# GaugeRev3.net
KiCad netlist of a schematic drawn in EAGLE
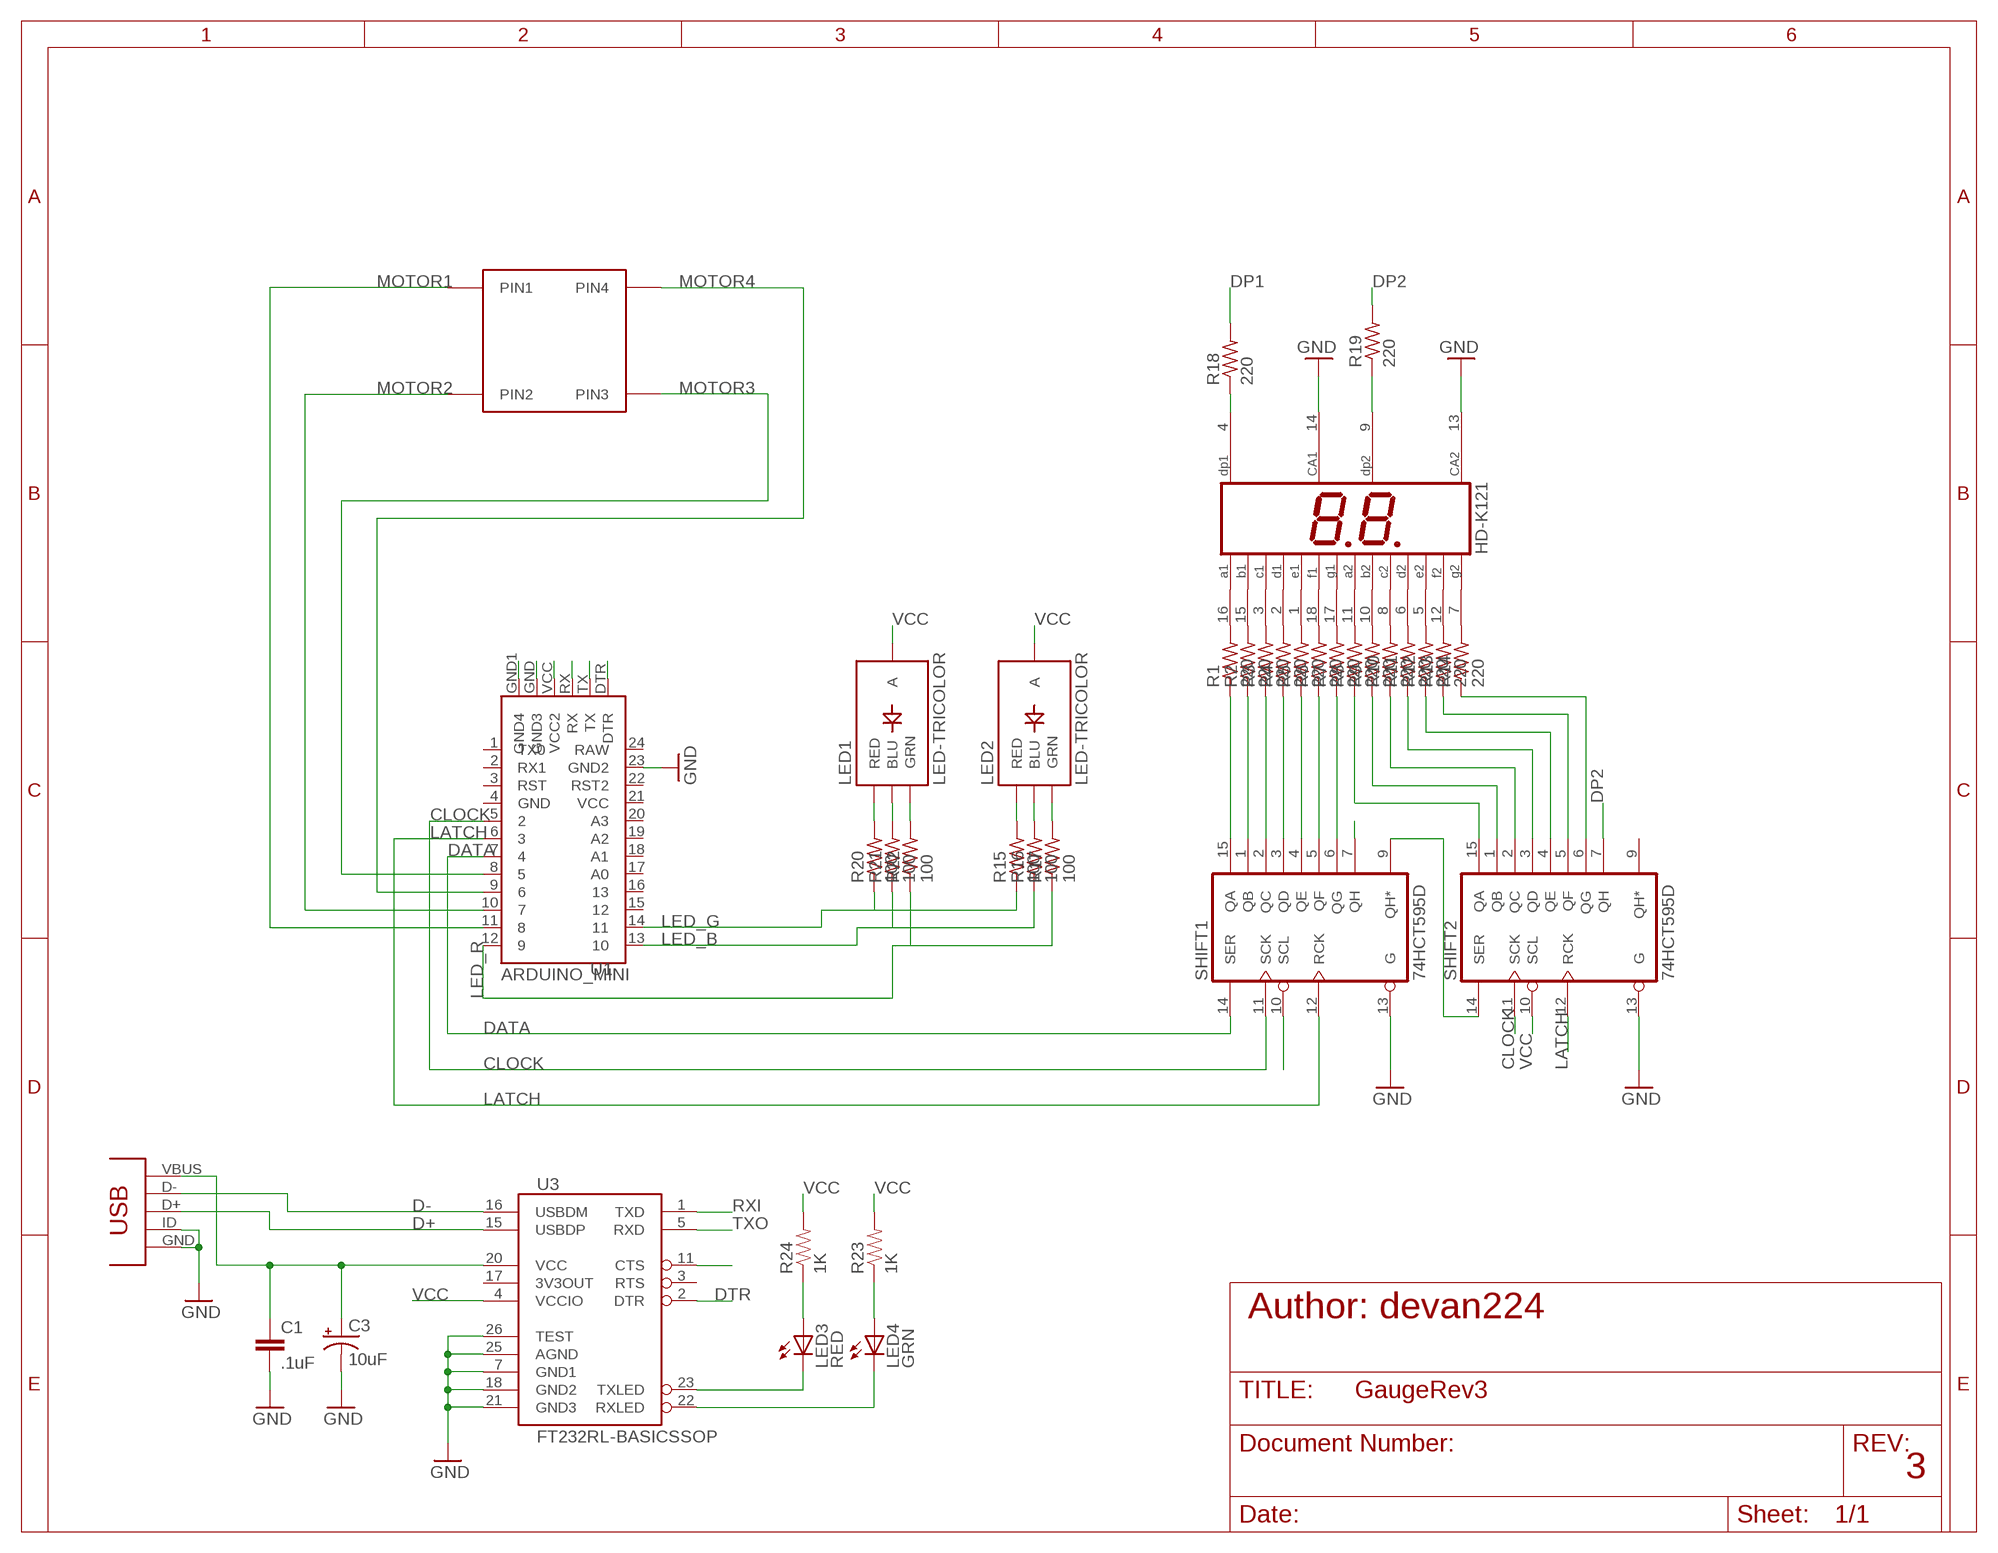
[diagram p0: schematic, sheet 1]

(export (version "E")
  (design (tool "Eeschema 10.0.6"))
  (components
    (comp (ref "C1")
      (value ".1uF")
      (footprint "eagle-import:1210")
      (libsource (lib "eagle-import") (part "CAP1210"))
    )
    (comp (ref "C3")
      (value "10uF")
      (footprint "eagle-import:EIA3216-KIT")
      (libsource (lib "eagle-import") (part "CAP_POL1206-KIT"))
    )
    (comp (ref "DIS2")
      (value "HD-K121")
      (footprint "eagle-import:HDSP-R")
      (libsource (lib "eagle-import") (part "HD-K121"))
    )
    (comp (ref "LED1")
      (value "LED-TRICOLOR")
      (footprint "eagle-import:LED-TRICOLOR-SMD")
      (libsource (lib "eagle-import") (part "LED-TRICOLOR"))
    )
    (comp (ref "LED2")
      (value "LED-TRICOLOR")
      (footprint "eagle-import:LED-TRICOLOR-SMD")
      (libsource (lib "eagle-import") (part "LED-TRICOLOR"))
    )
    (comp (ref "LED3")
      (value "RED")
      (footprint "eagle-import:LED-1206")
      (libsource (lib "eagle-import") (part "LED1206"))
    )
    (comp (ref "LED4")
      (value "GRN")
      (footprint "eagle-import:LED-1206")
      (libsource (lib "eagle-import") (part "LED1206"))
    )
    (comp (ref "R1")
      (value "220")
      (footprint "eagle-import:R1206")
      (libsource (lib "eagle-import") (part "R-US_R1206"))
    )
    (comp (ref "R2")
      (value "220")
      (footprint "eagle-import:R1206")
      (libsource (lib "eagle-import") (part "R-US_R1206"))
    )
    (comp (ref "R3")
      (value "220")
      (footprint "eagle-import:R1206")
      (libsource (lib "eagle-import") (part "R-US_R1206"))
    )
    (comp (ref "R4")
      (value "220")
      (footprint "eagle-import:R1206")
      (libsource (lib "eagle-import") (part "R-US_R1206"))
    )
    (comp (ref "R5")
      (value "220")
      (footprint "eagle-import:R1206")
      (libsource (lib "eagle-import") (part "R-US_R1206"))
    )
    (comp (ref "R6")
      (value "220")
      (footprint "eagle-import:R1206")
      (libsource (lib "eagle-import") (part "R-US_R1206"))
    )
    (comp (ref "R7")
      (value "220")
      (footprint "eagle-import:R1206")
      (libsource (lib "eagle-import") (part "R-US_R1206"))
    )
    (comp (ref "R8")
      (value "220")
      (footprint "eagle-import:R1206")
      (libsource (lib "eagle-import") (part "R-US_R1206"))
    )
    (comp (ref "R9")
      (value "220")
      (footprint "eagle-import:R1206")
      (libsource (lib "eagle-import") (part "R-US_R1206"))
    )
    (comp (ref "R10")
      (value "220")
      (footprint "eagle-import:R1206")
      (libsource (lib "eagle-import") (part "R-US_R1206"))
    )
    (comp (ref "R11")
      (value "220")
      (footprint "eagle-import:R1206")
      (libsource (lib "eagle-import") (part "R-US_R1206"))
    )
    (comp (ref "R12")
      (value "220")
      (footprint "eagle-import:R1206")
      (libsource (lib "eagle-import") (part "R-US_R1206"))
    )
    (comp (ref "R13")
      (value "220")
      (footprint "eagle-import:R1206")
      (libsource (lib "eagle-import") (part "R-US_R1206"))
    )
    (comp (ref "R14")
      (value "220")
      (footprint "eagle-import:R1206")
      (libsource (lib "eagle-import") (part "R-US_R1206"))
    )
    (comp (ref "R15")
      (value "100")
      (footprint "eagle-import:R1206")
      (libsource (lib "eagle-import") (part "R-US_R1206"))
    )
    (comp (ref "R16")
      (value "100")
      (footprint "eagle-import:R1206")
      (libsource (lib "eagle-import") (part "R-US_R1206"))
    )
    (comp (ref "R17")
      (value "100")
      (footprint "eagle-import:R1206")
      (libsource (lib "eagle-import") (part "R-US_R1206"))
    )
    (comp (ref "R18")
      (value "220")
      (footprint "eagle-import:R1206")
      (libsource (lib "eagle-import") (part "R-US_R1206"))
    )
    (comp (ref "R19")
      (value "220")
      (footprint "eagle-import:R1206")
      (libsource (lib "eagle-import") (part "R-US_R1206"))
    )
    (comp (ref "R20")
      (value "100")
      (footprint "eagle-import:R1206")
      (libsource (lib "eagle-import") (part "R-US_R1206"))
    )
    (comp (ref "R21")
      (value "100")
      (footprint "eagle-import:R1206")
      (libsource (lib "eagle-import") (part "R-US_R1206"))
    )
    (comp (ref "R22")
      (value "100")
      (footprint "eagle-import:R1206")
      (libsource (lib "eagle-import") (part "R-US_R1206"))
    )
    (comp (ref "R23")
      (value "1K")
      (footprint "eagle-import:1206")
      (libsource (lib "eagle-import") (part "RESISTOR1206"))
    )
    (comp (ref "R24")
      (value "1K")
      (footprint "eagle-import:1206")
      (libsource (lib "eagle-import") (part "RESISTOR1206"))
    )
    (comp (ref "SHIFT1")
      (value "74HCT595D")
      (footprint "eagle-import:SO16")
      (libsource (lib "eagle-import") (part "74595DHCT"))
    )
    (comp (ref "SHIFT2")
      (value "74HCT595D")
      (footprint "eagle-import:SO16")
      (libsource (lib "eagle-import") (part "74595DHCT"))
    )
    (comp (ref "U$1")
      (value "USB-MINI-VERT")
      (footprint "eagle-import:USB-MINI-VERT")
      (libsource (lib "eagle-import") (part "USB-MINI-VERT"))
    )
    (comp (ref "U1")
      (value "ARDUINO_MINI")
      (footprint "eagle-import:ARDUINO_MINI")
      (libsource (lib "eagle-import") (part "ARDUINO_MINI"))
    )
    (comp (ref "U2")
      (value "VID29")
      (footprint "eagle-import:VID29")
      (libsource (lib "eagle-import") (part "VID29"))
    )
    (comp (ref "U3")
      (value "FT232RL-BASICSSOP")
      (footprint "eagle-import:SSOP28DB")
      (libsource (lib "eagle-import") (part "FT232RL-BASICSSOP"))
    )
  )
  (nets
    (net (code "1") (name "/CLOCK") (class "Default")
      (node (ref "SHIFT1") (pin "11") (pinfunction "SCK_11") (pintype "input"))
      (node (ref "SHIFT2") (pin "11") (pinfunction "SCK_11") (pintype "input"))
      (node (ref "U1") (pin "5") (pinfunction "2_5") (pintype "bidirectional"))
    )
    (net (code "2") (name "/D+") (class "Default")
      (node (ref "U$1") (pin "D+") (pinfunction "D+_D+") (pintype "bidirectional"))
      (node (ref "U3") (pin "15") (pinfunction "USBDP_15") (pintype "bidirectional"))
    )
    (net (code "3") (name "/D-") (class "Default")
      (node (ref "U$1") (pin "D-") (pinfunction "D-_D-") (pintype "bidirectional"))
      (node (ref "U3") (pin "16") (pinfunction "USBDM_16") (pintype "bidirectional"))
    )
    (net (code "4") (name "/DATA") (class "Default")
      (node (ref "SHIFT1") (pin "14") (pinfunction "SER_14") (pintype "input"))
      (node (ref "U1") (pin "7") (pinfunction "4_7") (pintype "bidirectional"))
    )
    (net (code "5") (name "/DP1") (class "Default")
      (node (ref "R18") (pin "2") (pinfunction "2_2") (pintype "passive"))
      (node (ref "SHIFT1") (pin "7") (pinfunction "QH_7") (pintype "tri_state"))
    )
    (net (code "6") (name "/DP2") (class "Default")
      (node (ref "R19") (pin "2") (pinfunction "2_2") (pintype "passive"))
      (node (ref "SHIFT2") (pin "7") (pinfunction "QH_7") (pintype "tri_state"))
    )
    (net (code "7") (name "/DTR") (class "Default")
      (node (ref "U1") (pin "DTR") (pinfunction "DTR_DTR") (pintype "bidirectional"))
      (node (ref "U3") (pin "2") (pinfunction "DTR_2") (pintype "bidirectional"))
    )
    (net (code "8") (name "/LATCH") (class "Default")
      (node (ref "SHIFT1") (pin "12") (pinfunction "RCK_12") (pintype "input"))
      (node (ref "SHIFT2") (pin "12") (pinfunction "RCK_12") (pintype "input"))
      (node (ref "U1") (pin "6") (pinfunction "3_6") (pintype "bidirectional"))
    )
    (net (code "9") (name "/LED_B") (class "Default")
      (node (ref "R16") (pin "1") (pinfunction "1_1") (pintype "passive"))
      (node (ref "R21") (pin "1") (pinfunction "1_1") (pintype "passive"))
      (node (ref "U1") (pin "13") (pinfunction "10_13") (pintype "bidirectional"))
    )
    (net (code "10") (name "/LED_G") (class "Default")
      (node (ref "R15") (pin "1") (pinfunction "1_1") (pintype "passive"))
      (node (ref "R20") (pin "1") (pinfunction "1_1") (pintype "passive"))
      (node (ref "U1") (pin "14") (pinfunction "11_14") (pintype "bidirectional"))
    )
    (net (code "11") (name "/LED_R") (class "Default")
      (node (ref "R17") (pin "1") (pinfunction "1_1") (pintype "passive"))
      (node (ref "R22") (pin "1") (pinfunction "1_1") (pintype "passive"))
      (node (ref "U1") (pin "12") (pinfunction "9_12") (pintype "bidirectional"))
    )
    (net (code "12") (name "/MOTOR1") (class "Default")
      (node (ref "U1") (pin "11") (pinfunction "8_11") (pintype "bidirectional"))
      (node (ref "U2") (pin "PIN1") (pinfunction "PIN1_PIN1") (pintype "bidirectional"))
    )
    (net (code "13") (name "/MOTOR2") (class "Default")
      (node (ref "U1") (pin "10") (pinfunction "7_10") (pintype "bidirectional"))
      (node (ref "U2") (pin "PIN2") (pinfunction "PIN2_PIN2") (pintype "bidirectional"))
    )
    (net (code "14") (name "/MOTOR3") (class "Default")
      (node (ref "U1") (pin "8") (pinfunction "5_8") (pintype "bidirectional"))
      (node (ref "U2") (pin "PIN3") (pinfunction "PIN3_PIN3") (pintype "bidirectional"))
    )
    (net (code "15") (name "/MOTOR4") (class "Default")
      (node (ref "U1") (pin "9") (pinfunction "6_9") (pintype "bidirectional"))
      (node (ref "U2") (pin "PIN4") (pinfunction "PIN4_PIN4") (pintype "bidirectional"))
    )
    (net (code "16") (name "/RXI") (class "Default")
      (node (ref "U1") (pin "RX") (pinfunction "RX_RX") (pintype "bidirectional"))
      (node (ref "U3") (pin "1") (pinfunction "TXD_1") (pintype "output"))
    )
    (net (code "17") (name "/TXO") (class "Default")
      (node (ref "U1") (pin "TX") (pinfunction "TX_TX") (pintype "bidirectional"))
      (node (ref "U3") (pin "5") (pinfunction "RXD_5") (pintype "input"))
    )
    (net (code "18") (name "/VCC") (class "Default")
      (node (ref "LED1") (pin "A") (pinfunction "A_A") (pintype "bidirectional"))
      (node (ref "LED2") (pin "A") (pinfunction "A_A") (pintype "bidirectional"))
      (node (ref "R23") (pin "2") (pinfunction "2_2") (pintype "passive"))
      (node (ref "R24") (pin "2") (pinfunction "2_2") (pintype "passive"))
      (node (ref "SHIFT1") (pin "10") (pinfunction "SCL_10") (pintype "input"))
      (node (ref "SHIFT2") (pin "10") (pinfunction "SCL_10") (pintype "input"))
      (node (ref "U1") (pin "VCC") (pinfunction "VCC2_VCC") (pintype "bidirectional"))
      (node (ref "U3") (pin "4") (pinfunction "VCCIO_4") (pintype "power_in"))
    )
    (net (code "19") (name "GND") (class "Default")
      (node (ref "C1") (pin "2") (pinfunction "2_2") (pintype "passive"))
      (node (ref "C3") (pin "C") (pinfunction "-_C") (pintype "passive"))
      (node (ref "DIS2") (pin "13") (pinfunction "CA2_13") (pintype "passive"))
      (node (ref "DIS2") (pin "14") (pinfunction "CA1_14") (pintype "passive"))
      (node (ref "SHIFT1") (pin "13") (pinfunction "G_13") (pintype "input"))
      (node (ref "SHIFT2") (pin "13") (pinfunction "G_13") (pintype "input"))
      (node (ref "U$1") (pin "GND") (pinfunction "GND_GND") (pintype "bidirectional"))
      (node (ref "U$1") (pin "ID") (pinfunction "ID_ID") (pintype "bidirectional"))
      (node (ref "U1") (pin "23") (pinfunction "GND2_23") (pintype "bidirectional"))
      (node (ref "U1") (pin "GND") (pinfunction "GND3_GND") (pintype "bidirectional"))
      (node (ref "U1") (pin "GND1") (pinfunction "GND4_GND1") (pintype "bidirectional"))
      (node (ref "U3") (pin "11") (pinfunction "CTS_11") (pintype "bidirectional"))
      (node (ref "U3") (pin "18") (pinfunction "GND2_18") (pintype "power_in"))
      (node (ref "U3") (pin "21") (pinfunction "GND3_21") (pintype "power_in"))
      (node (ref "U3") (pin "25") (pinfunction "AGND_25") (pintype "power_in"))
      (node (ref "U3") (pin "26") (pinfunction "TEST_26") (pintype "input"))
      (node (ref "U3") (pin "7") (pinfunction "GND1_7") (pintype "power_in"))
    )
    (net (code "20") (name "Net-(C3-+)") (class "Default")
      (node (ref "C1") (pin "1") (pinfunction "1_1") (pintype "passive"))
      (node (ref "C3") (pin "A") (pinfunction "+_A") (pintype "passive"))
      (node (ref "U$1") (pin "VBUS") (pinfunction "VBUS_VBUS") (pintype "bidirectional"))
      (node (ref "U3") (pin "20") (pinfunction "VCC_20") (pintype "power_in"))
    )
    (net (code "21") (name "Net-(DIS2-A1)") (class "Default")
      (node (ref "DIS2") (pin "16") (pinfunction "A1_16") (pintype "passive"))
      (node (ref "R1") (pin "2") (pinfunction "2_2") (pintype "passive"))
    )
    (net (code "22") (name "Net-(DIS2-A2)") (class "Default")
      (node (ref "DIS2") (pin "11") (pinfunction "A2_11") (pintype "passive"))
      (node (ref "R8") (pin "2") (pinfunction "2_2") (pintype "passive"))
    )
    (net (code "23") (name "Net-(DIS2-B1)") (class "Default")
      (node (ref "DIS2") (pin "15") (pinfunction "B1_15") (pintype "passive"))
      (node (ref "R2") (pin "2") (pinfunction "2_2") (pintype "passive"))
    )
    (net (code "24") (name "Net-(DIS2-B2)") (class "Default")
      (node (ref "DIS2") (pin "10") (pinfunction "B2_10") (pintype "passive"))
      (node (ref "R9") (pin "2") (pinfunction "2_2") (pintype "passive"))
    )
    (net (code "25") (name "Net-(DIS2-C1)") (class "Default")
      (node (ref "DIS2") (pin "3") (pinfunction "C1_3") (pintype "passive"))
      (node (ref "R3") (pin "2") (pinfunction "2_2") (pintype "passive"))
    )
    (net (code "26") (name "Net-(DIS2-C2)") (class "Default")
      (node (ref "DIS2") (pin "8") (pinfunction "C2_8") (pintype "passive"))
      (node (ref "R10") (pin "2") (pinfunction "2_2") (pintype "passive"))
    )
    (net (code "27") (name "Net-(DIS2-D1)") (class "Default")
      (node (ref "DIS2") (pin "2") (pinfunction "D1_2") (pintype "passive"))
      (node (ref "R4") (pin "2") (pinfunction "2_2") (pintype "passive"))
    )
    (net (code "28") (name "Net-(DIS2-D2)") (class "Default")
      (node (ref "DIS2") (pin "6") (pinfunction "D2_6") (pintype "passive"))
      (node (ref "R11") (pin "2") (pinfunction "2_2") (pintype "passive"))
    )
    (net (code "29") (name "Net-(DIS2-DP1)") (class "Default")
      (node (ref "DIS2") (pin "4") (pinfunction "DP1_4") (pintype "passive"))
      (node (ref "R18") (pin "1") (pinfunction "1_1") (pintype "passive"))
    )
    (net (code "30") (name "Net-(DIS2-DP2)") (class "Default")
      (node (ref "DIS2") (pin "9") (pinfunction "DP2_9") (pintype "passive"))
      (node (ref "R19") (pin "1") (pinfunction "1_1") (pintype "passive"))
    )
    (net (code "31") (name "Net-(DIS2-E1)") (class "Default")
      (node (ref "DIS2") (pin "1") (pinfunction "E1_1") (pintype "passive"))
      (node (ref "R5") (pin "2") (pinfunction "2_2") (pintype "passive"))
    )
    (net (code "32") (name "Net-(DIS2-E2)") (class "Default")
      (node (ref "DIS2") (pin "5") (pinfunction "E2_5") (pintype "passive"))
      (node (ref "R12") (pin "2") (pinfunction "2_2") (pintype "passive"))
    )
    (net (code "33") (name "Net-(DIS2-F1)") (class "Default")
      (node (ref "DIS2") (pin "18") (pinfunction "F1_18") (pintype "passive"))
      (node (ref "R6") (pin "2") (pinfunction "2_2") (pintype "passive"))
    )
    (net (code "34") (name "Net-(DIS2-F2)") (class "Default")
      (node (ref "DIS2") (pin "12") (pinfunction "F2_12") (pintype "passive"))
      (node (ref "R13") (pin "2") (pinfunction "2_2") (pintype "passive"))
    )
    (net (code "35") (name "Net-(DIS2-G1)") (class "Default")
      (node (ref "DIS2") (pin "17") (pinfunction "G1_17") (pintype "passive"))
      (node (ref "R7") (pin "2") (pinfunction "2_2") (pintype "passive"))
    )
    (net (code "36") (name "Net-(DIS2-G2)") (class "Default")
      (node (ref "DIS2") (pin "7") (pinfunction "G2_7") (pintype "passive"))
      (node (ref "R14") (pin "2") (pinfunction "2_2") (pintype "passive"))
    )
    (net (code "37") (name "Net-(LED1-BLU)") (class "Default")
      (node (ref "LED1") (pin "B") (pinfunction "BLU_B") (pintype "bidirectional"))
      (node (ref "R21") (pin "2") (pinfunction "2_2") (pintype "passive"))
    )
    (net (code "38") (name "Net-(LED1-GRN)") (class "Default")
      (node (ref "LED1") (pin "G") (pinfunction "GRN_G") (pintype "bidirectional"))
      (node (ref "R22") (pin "2") (pinfunction "2_2") (pintype "passive"))
    )
    (net (code "39") (name "Net-(LED1-RED)") (class "Default")
      (node (ref "LED1") (pin "R") (pinfunction "RED_R") (pintype "bidirectional"))
      (node (ref "R20") (pin "2") (pinfunction "2_2") (pintype "passive"))
    )
    (net (code "40") (name "Net-(LED2-BLU)") (class "Default")
      (node (ref "LED2") (pin "B") (pinfunction "BLU_B") (pintype "bidirectional"))
      (node (ref "R16") (pin "2") (pinfunction "2_2") (pintype "passive"))
    )
    (net (code "41") (name "Net-(LED2-GRN)") (class "Default")
      (node (ref "LED2") (pin "G") (pinfunction "GRN_G") (pintype "bidirectional"))
      (node (ref "R17") (pin "2") (pinfunction "2_2") (pintype "passive"))
    )
    (net (code "42") (name "Net-(LED2-RED)") (class "Default")
      (node (ref "LED2") (pin "R") (pinfunction "RED_R") (pintype "bidirectional"))
      (node (ref "R15") (pin "2") (pinfunction "2_2") (pintype "passive"))
    )
    (net (code "43") (name "Net-(LED3-PadA)") (class "Default")
      (node (ref "LED3") (pin "A") (pinfunction "A_A") (pintype "passive"))
      (node (ref "R24") (pin "1") (pinfunction "1_1") (pintype "passive"))
    )
    (net (code "44") (name "Net-(LED4-PadA)") (class "Default")
      (node (ref "LED4") (pin "A") (pinfunction "A_A") (pintype "passive"))
      (node (ref "R23") (pin "1") (pinfunction "1_1") (pintype "passive"))
    )
    (net (code "45") (name "Net-(SHIFT1A-QA)") (class "Default")
      (node (ref "R1") (pin "1") (pinfunction "1_1") (pintype "passive"))
      (node (ref "SHIFT1") (pin "15") (pinfunction "QA_15") (pintype "tri_state"))
    )
    (net (code "46") (name "Net-(SHIFT1A-QB)") (class "Default")
      (node (ref "R2") (pin "1") (pinfunction "1_1") (pintype "passive"))
      (node (ref "SHIFT1") (pin "1") (pinfunction "QB_1") (pintype "tri_state"))
    )
    (net (code "47") (name "Net-(SHIFT1A-QC)") (class "Default")
      (node (ref "R3") (pin "1") (pinfunction "1_1") (pintype "passive"))
      (node (ref "SHIFT1") (pin "2") (pinfunction "QC_2") (pintype "tri_state"))
    )
    (net (code "48") (name "Net-(SHIFT1A-QD)") (class "Default")
      (node (ref "R4") (pin "1") (pinfunction "1_1") (pintype "passive"))
      (node (ref "SHIFT1") (pin "3") (pinfunction "QD_3") (pintype "tri_state"))
    )
    (net (code "49") (name "Net-(SHIFT1A-QE)") (class "Default")
      (node (ref "R5") (pin "1") (pinfunction "1_1") (pintype "passive"))
      (node (ref "SHIFT1") (pin "4") (pinfunction "QE_4") (pintype "tri_state"))
    )
    (net (code "50") (name "Net-(SHIFT1A-QF)") (class "Default")
      (node (ref "R6") (pin "1") (pinfunction "1_1") (pintype "passive"))
      (node (ref "SHIFT1") (pin "5") (pinfunction "QF_5") (pintype "tri_state"))
    )
    (net (code "51") (name "Net-(SHIFT1A-QG)") (class "Default")
      (node (ref "R7") (pin "1") (pinfunction "1_1") (pintype "passive"))
      (node (ref "SHIFT1") (pin "6") (pinfunction "QG_6") (pintype "tri_state"))
    )
    (net (code "52") (name "Net-(SHIFT1A-QH*)") (class "Default")
      (node (ref "SHIFT1") (pin "9") (pinfunction "QH*_9") (pintype "tri_state"))
      (node (ref "SHIFT2") (pin "14") (pinfunction "SER_14") (pintype "input"))
    )
    (net (code "53") (name "Net-(SHIFT2A-QA)") (class "Default")
      (node (ref "R8") (pin "1") (pinfunction "1_1") (pintype "passive"))
      (node (ref "SHIFT2") (pin "15") (pinfunction "QA_15") (pintype "tri_state"))
    )
    (net (code "54") (name "Net-(SHIFT2A-QB)") (class "Default")
      (node (ref "R9") (pin "1") (pinfunction "1_1") (pintype "passive"))
      (node (ref "SHIFT2") (pin "1") (pinfunction "QB_1") (pintype "tri_state"))
    )
    (net (code "55") (name "Net-(SHIFT2A-QC)") (class "Default")
      (node (ref "R10") (pin "1") (pinfunction "1_1") (pintype "passive"))
      (node (ref "SHIFT2") (pin "2") (pinfunction "QC_2") (pintype "tri_state"))
    )
    (net (code "56") (name "Net-(SHIFT2A-QD)") (class "Default")
      (node (ref "R11") (pin "1") (pinfunction "1_1") (pintype "passive"))
      (node (ref "SHIFT2") (pin "3") (pinfunction "QD_3") (pintype "tri_state"))
    )
    (net (code "57") (name "Net-(SHIFT2A-QE)") (class "Default")
      (node (ref "R12") (pin "1") (pinfunction "1_1") (pintype "passive"))
      (node (ref "SHIFT2") (pin "4") (pinfunction "QE_4") (pintype "tri_state"))
    )
    (net (code "58") (name "Net-(SHIFT2A-QF)") (class "Default")
      (node (ref "R13") (pin "1") (pinfunction "1_1") (pintype "passive"))
      (node (ref "SHIFT2") (pin "5") (pinfunction "QF_5") (pintype "tri_state"))
    )
    (net (code "59") (name "Net-(SHIFT2A-QG)") (class "Default")
      (node (ref "R14") (pin "1") (pinfunction "1_1") (pintype "passive"))
      (node (ref "SHIFT2") (pin "6") (pinfunction "QG_6") (pintype "tri_state"))
    )
    (net (code "60") (name "Net-(U3-RXLED)") (class "Default")
      (node (ref "LED4") (pin "C") (pinfunction "C_C") (pintype "passive"))
      (node (ref "U3") (pin "22") (pinfunction "RXLED_22") (pintype "bidirectional"))
    )
    (net (code "61") (name "Net-(U3-TXLED)") (class "Default")
      (node (ref "LED3") (pin "C") (pinfunction "C_C") (pintype "passive"))
      (node (ref "U3") (pin "23") (pinfunction "TXLED_23") (pintype "bidirectional"))
    )
    (net (code "62") (name "unconnected-(SHIFT2A-QH*-Pad9)") (class "Default")
      (node (ref "SHIFT2") (pin "9") (pinfunction "QH*_9") (pintype "tri_state"))
    )
    (net (code "63") (name "unconnected-(U1-12-Pad15)") (class "Default")
      (node (ref "U1") (pin "15") (pinfunction "12_15") (pintype "bidirectional"))
    )
    (net (code "64") (name "unconnected-(U1-13-Pad16)") (class "Default")
      (node (ref "U1") (pin "16") (pinfunction "13_16") (pintype "bidirectional"))
    )
    (net (code "65") (name "unconnected-(U1-A0-Pad17)") (class "Default")
      (node (ref "U1") (pin "17") (pinfunction "A0_17") (pintype "bidirectional"))
    )
    (net (code "66") (name "unconnected-(U1-A1-Pad18)") (class "Default")
      (node (ref "U1") (pin "18") (pinfunction "A1_18") (pintype "bidirectional"))
    )
    (net (code "67") (name "unconnected-(U1-A2-Pad19)") (class "Default")
      (node (ref "U1") (pin "19") (pinfunction "A2_19") (pintype "bidirectional"))
    )
    (net (code "68") (name "unconnected-(U1-A3-Pad20)") (class "Default")
      (node (ref "U1") (pin "20") (pinfunction "A3_20") (pintype "bidirectional"))
    )
    (net (code "69") (name "unconnected-(U1-GND-Pad4)") (class "Default")
      (node (ref "U1") (pin "4") (pinfunction "GND_4") (pintype "bidirectional"))
    )
    (net (code "70") (name "unconnected-(U1-RAW-Pad24)") (class "Default")
      (node (ref "U1") (pin "24") (pinfunction "RAW_24") (pintype "bidirectional"))
    )
    (net (code "71") (name "unconnected-(U1-RST-Pad3)") (class "Default")
      (node (ref "U1") (pin "3") (pinfunction "RST_3") (pintype "bidirectional"))
    )
    (net (code "72") (name "unconnected-(U1-RST2-Pad22)") (class "Default")
      (node (ref "U1") (pin "22") (pinfunction "RST2_22") (pintype "bidirectional"))
    )
    (net (code "73") (name "unconnected-(U1-RX1-Pad2)") (class "Default")
      (node (ref "U1") (pin "2") (pinfunction "RX1_2") (pintype "bidirectional"))
    )
    (net (code "74") (name "unconnected-(U1-TX0-Pad1)") (class "Default")
      (node (ref "U1") (pin "1") (pinfunction "TX0_1") (pintype "bidirectional"))
    )
    (net (code "75") (name "unconnected-(U1-VCC-Pad21)") (class "Default")
      (node (ref "U1") (pin "21") (pinfunction "VCC_21") (pintype "bidirectional"))
    )
    (net (code "76") (name "unconnected-(U3-3V3OUT-Pad17)") (class "Default")
      (node (ref "U3") (pin "17") (pinfunction "3V3OUT_17") (pintype "output"))
    )
    (net (code "77") (name "unconnected-(U3-RTS-Pad3)") (class "Default")
      (node (ref "U3") (pin "3") (pinfunction "RTS_3") (pintype "bidirectional"))
    )
  )
)
